# ou6_cs-ctrl_V1_0.net
KiCad netlist of a schematic drawn in EAGLE
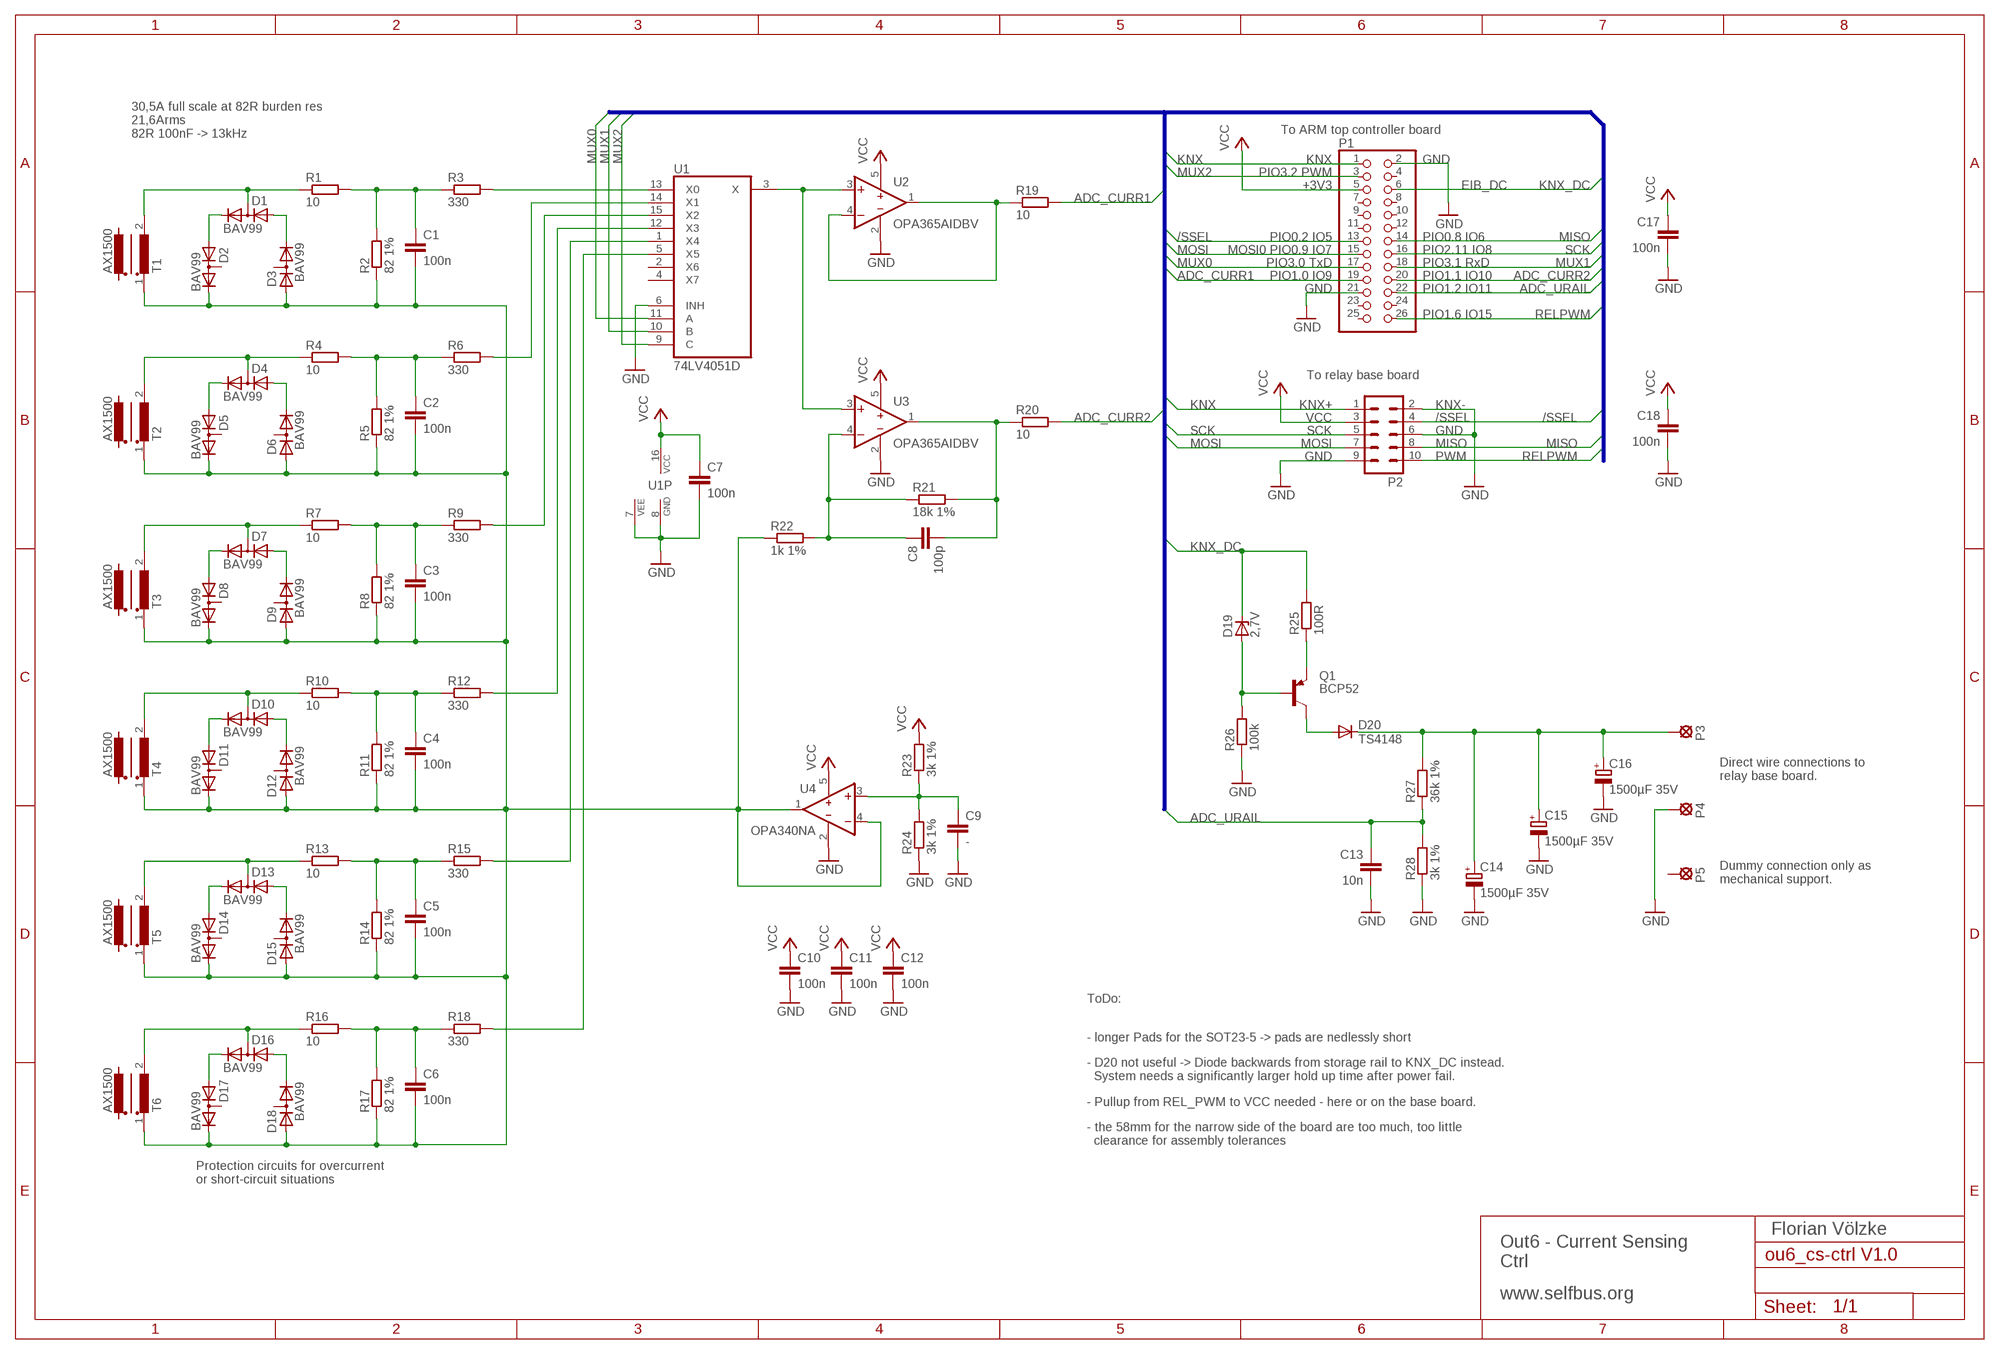
[diagram p0: schematic, sheet 1]

(export (version "E")
  (design (tool "Eeschema 10.0.6"))
  (components
    (comp (ref "C1")
      (value "100n")
      (footprint "eagle-import:R0805M")
      (libsource (lib "eagle-import") (part "C-EUC0805M"))
    )
    (comp (ref "C2")
      (value "100n")
      (footprint "eagle-import:R0805M")
      (libsource (lib "eagle-import") (part "C-EUC0805M"))
    )
    (comp (ref "C3")
      (value "100n")
      (footprint "eagle-import:R0805M")
      (libsource (lib "eagle-import") (part "C-EUC0805M"))
    )
    (comp (ref "C4")
      (value "100n")
      (footprint "eagle-import:R0805M")
      (libsource (lib "eagle-import") (part "C-EUC0805M"))
    )
    (comp (ref "C5")
      (value "100n")
      (footprint "eagle-import:R0805M")
      (libsource (lib "eagle-import") (part "C-EUC0805M"))
    )
    (comp (ref "C6")
      (value "100n")
      (footprint "eagle-import:R0805M")
      (libsource (lib "eagle-import") (part "C-EUC0805M"))
    )
    (comp (ref "C7")
      (value "100n")
      (footprint "eagle-import:R0805M")
      (libsource (lib "eagle-import") (part "C-EUC0805M"))
    )
    (comp (ref "C8")
      (value "100p")
      (footprint "eagle-import:R0805M")
      (libsource (lib "eagle-import") (part "C-EUC0805M"))
    )
    (comp (ref "C9")
      (value "-")
      (footprint "eagle-import:R0805M")
      (libsource (lib "eagle-import") (part "C-EUC0805M"))
    )
    (comp (ref "C10")
      (value "100n")
      (footprint "eagle-import:R0805M")
      (libsource (lib "eagle-import") (part "C-EUC0805M"))
    )
    (comp (ref "C11")
      (value "100n")
      (footprint "eagle-import:R0805M")
      (libsource (lib "eagle-import") (part "C-EUC0805M"))
    )
    (comp (ref "C12")
      (value "100n")
      (footprint "eagle-import:R0805M")
      (libsource (lib "eagle-import") (part "C-EUC0805M"))
    )
    (comp (ref "C13")
      (value "10n")
      (footprint "eagle-import:R0805M")
      (libsource (lib "eagle-import") (part "C-EUC0805M"))
    )
    (comp (ref "C14")
      (value "1500µF 35V")
      (footprint "eagle-import:E5-13-30")
      (libsource (lib "eagle-import") (part "CPOL-EUE5-13-30"))
    )
    (comp (ref "C15")
      (value "1500µF 35V")
      (footprint "eagle-import:E5-13-30")
      (libsource (lib "eagle-import") (part "CPOL-EUE5-13-30"))
    )
    (comp (ref "C16")
      (value "1500µF 35V")
      (footprint "eagle-import:E5-13-30")
      (libsource (lib "eagle-import") (part "CPOL-EUE5-13-30"))
    )
    (comp (ref "C17")
      (value "100n")
      (footprint "eagle-import:R0805M")
      (libsource (lib "eagle-import") (part "C-EUC0805M"))
    )
    (comp (ref "C18")
      (value "100n")
      (footprint "eagle-import:R0805M")
      (libsource (lib "eagle-import") (part "C-EUC0805M"))
    )
    (comp (ref "D1")
      (value "BAV99")
      (footprint "eagle-import:SOT23")
      (libsource (lib "eagle-import") (part "DIODE_2CACA-SOT23"))
    )
    (comp (ref "D2")
      (value "BAV99")
      (footprint "eagle-import:SOT23")
      (libsource (lib "eagle-import") (part "DIODE_2CACA-SOT23"))
    )
    (comp (ref "D3")
      (value "BAV99")
      (footprint "eagle-import:SOT23")
      (libsource (lib "eagle-import") (part "DIODE_2CACA-SOT23"))
    )
    (comp (ref "D4")
      (value "BAV99")
      (footprint "eagle-import:SOT23")
      (libsource (lib "eagle-import") (part "DIODE_2CACA-SOT23"))
    )
    (comp (ref "D5")
      (value "BAV99")
      (footprint "eagle-import:SOT23")
      (libsource (lib "eagle-import") (part "DIODE_2CACA-SOT23"))
    )
    (comp (ref "D6")
      (value "BAV99")
      (footprint "eagle-import:SOT23")
      (libsource (lib "eagle-import") (part "DIODE_2CACA-SOT23"))
    )
    (comp (ref "D7")
      (value "BAV99")
      (footprint "eagle-import:SOT23")
      (libsource (lib "eagle-import") (part "DIODE_2CACA-SOT23"))
    )
    (comp (ref "D8")
      (value "BAV99")
      (footprint "eagle-import:SOT23")
      (libsource (lib "eagle-import") (part "DIODE_2CACA-SOT23"))
    )
    (comp (ref "D9")
      (value "BAV99")
      (footprint "eagle-import:SOT23")
      (libsource (lib "eagle-import") (part "DIODE_2CACA-SOT23"))
    )
    (comp (ref "D10")
      (value "BAV99")
      (footprint "eagle-import:SOT23")
      (libsource (lib "eagle-import") (part "DIODE_2CACA-SOT23"))
    )
    (comp (ref "D11")
      (value "BAV99")
      (footprint "eagle-import:SOT23")
      (libsource (lib "eagle-import") (part "DIODE_2CACA-SOT23"))
    )
    (comp (ref "D12")
      (value "BAV99")
      (footprint "eagle-import:SOT23")
      (libsource (lib "eagle-import") (part "DIODE_2CACA-SOT23"))
    )
    (comp (ref "D13")
      (value "BAV99")
      (footprint "eagle-import:SOT23")
      (libsource (lib "eagle-import") (part "DIODE_2CACA-SOT23"))
    )
    (comp (ref "D14")
      (value "BAV99")
      (footprint "eagle-import:SOT23")
      (libsource (lib "eagle-import") (part "DIODE_2CACA-SOT23"))
    )
    (comp (ref "D15")
      (value "BAV99")
      (footprint "eagle-import:SOT23")
      (libsource (lib "eagle-import") (part "DIODE_2CACA-SOT23"))
    )
    (comp (ref "D16")
      (value "BAV99")
      (footprint "eagle-import:SOT23")
      (libsource (lib "eagle-import") (part "DIODE_2CACA-SOT23"))
    )
    (comp (ref "D17")
      (value "BAV99")
      (footprint "eagle-import:SOT23")
      (libsource (lib "eagle-import") (part "DIODE_2CACA-SOT23"))
    )
    (comp (ref "D18")
      (value "BAV99")
      (footprint "eagle-import:SOT23")
      (libsource (lib "eagle-import") (part "DIODE_2CACA-SOT23"))
    )
    (comp (ref "D19")
      (value "2,7V")
      (footprint "eagle-import:SOT23")
      (libsource (lib "eagle-import") (part "ZENER-DIODESOT23"))
    )
    (comp (ref "D20")
      (value "TS4148")
      (footprint "eagle-import:MINIMELF")
      (libsource (lib "eagle-import") (part "DIODE-MINIMELF"))
    )
    (comp (ref "P1")
      (value "PINHD-2X13SMD")
      (footprint "eagle-import:2X13SMD")
      (libsource (lib "eagle-import") (part "PINHD-2X13SMD"))
    )
    (comp (ref "P2")
      (value "ML10")
      (footprint "eagle-import:ML10")
      (libsource (lib "eagle-import") (part "ML10"))
    )
    (comp (ref "P3")
      (value "SE1.5")
      (footprint "eagle-import:SE15")
      (libsource (lib "eagle-import") (part "SE1.5"))
    )
    (comp (ref "P4")
      (value "SE1.5")
      (footprint "eagle-import:SE15")
      (libsource (lib "eagle-import") (part "SE1.5"))
    )
    (comp (ref "P5")
      (value "SE1.5")
      (footprint "eagle-import:SE15")
      (libsource (lib "eagle-import") (part "SE1.5"))
    )
    (comp (ref "Q1")
      (value "BCP52")
      (footprint "eagle-import:SOT223")
      (libsource (lib "eagle-import") (part "FZT753SMD"))
    )
    (comp (ref "R1")
      (value "10")
      (footprint "eagle-import:R0805M")
      (libsource (lib "eagle-import") (part "R-EU_R0805M"))
    )
    (comp (ref "R2")
      (value "82 1%")
      (footprint "eagle-import:R0805M")
      (libsource (lib "eagle-import") (part "R-EU_R0805M"))
    )
    (comp (ref "R3")
      (value "330")
      (footprint "eagle-import:R0805M")
      (libsource (lib "eagle-import") (part "R-EU_R0805M"))
    )
    (comp (ref "R4")
      (value "10")
      (footprint "eagle-import:R0805M")
      (libsource (lib "eagle-import") (part "R-EU_R0805M"))
    )
    (comp (ref "R5")
      (value "82 1%")
      (footprint "eagle-import:R0805M")
      (libsource (lib "eagle-import") (part "R-EU_R0805M"))
    )
    (comp (ref "R6")
      (value "330")
      (footprint "eagle-import:R0805M")
      (libsource (lib "eagle-import") (part "R-EU_R0805M"))
    )
    (comp (ref "R7")
      (value "10")
      (footprint "eagle-import:R0805M")
      (libsource (lib "eagle-import") (part "R-EU_R0805M"))
    )
    (comp (ref "R8")
      (value "82 1%")
      (footprint "eagle-import:R0805M")
      (libsource (lib "eagle-import") (part "R-EU_R0805M"))
    )
    (comp (ref "R9")
      (value "330")
      (footprint "eagle-import:R0805M")
      (libsource (lib "eagle-import") (part "R-EU_R0805M"))
    )
    (comp (ref "R10")
      (value "10")
      (footprint "eagle-import:R0805M")
      (libsource (lib "eagle-import") (part "R-EU_R0805M"))
    )
    (comp (ref "R11")
      (value "82 1%")
      (footprint "eagle-import:R0805M")
      (libsource (lib "eagle-import") (part "R-EU_R0805M"))
    )
    (comp (ref "R12")
      (value "330")
      (footprint "eagle-import:R0805M")
      (libsource (lib "eagle-import") (part "R-EU_R0805M"))
    )
    (comp (ref "R13")
      (value "10")
      (footprint "eagle-import:R0805M")
      (libsource (lib "eagle-import") (part "R-EU_R0805M"))
    )
    (comp (ref "R14")
      (value "82 1%")
      (footprint "eagle-import:R0805M")
      (libsource (lib "eagle-import") (part "R-EU_R0805M"))
    )
    (comp (ref "R15")
      (value "330")
      (footprint "eagle-import:R0805M")
      (libsource (lib "eagle-import") (part "R-EU_R0805M"))
    )
    (comp (ref "R16")
      (value "10")
      (footprint "eagle-import:R0805M")
      (libsource (lib "eagle-import") (part "R-EU_R0805M"))
    )
    (comp (ref "R17")
      (value "82 1%")
      (footprint "eagle-import:R0805M")
      (libsource (lib "eagle-import") (part "R-EU_R0805M"))
    )
    (comp (ref "R18")
      (value "330")
      (footprint "eagle-import:R0805M")
      (libsource (lib "eagle-import") (part "R-EU_R0805M"))
    )
    (comp (ref "R19")
      (value "10")
      (footprint "eagle-import:R0805M")
      (libsource (lib "eagle-import") (part "R-EU_R0805M"))
    )
    (comp (ref "R20")
      (value "10")
      (footprint "eagle-import:R0805M")
      (libsource (lib "eagle-import") (part "R-EU_R0805M"))
    )
    (comp (ref "R21")
      (value "18k 1%")
      (footprint "eagle-import:R0805M")
      (libsource (lib "eagle-import") (part "R-EU_R0805M"))
    )
    (comp (ref "R22")
      (value "1k 1%")
      (footprint "eagle-import:R0805M")
      (libsource (lib "eagle-import") (part "R-EU_R0805M"))
    )
    (comp (ref "R23")
      (value "3k 1%")
      (footprint "eagle-import:R0805M")
      (libsource (lib "eagle-import") (part "R-EU_R0805M"))
    )
    (comp (ref "R24")
      (value "3k 1%")
      (footprint "eagle-import:R0805M")
      (libsource (lib "eagle-import") (part "R-EU_R0805M"))
    )
    (comp (ref "R25")
      (value "100R")
      (footprint "eagle-import:R0805M")
      (libsource (lib "eagle-import") (part "R-EU_R0805M"))
    )
    (comp (ref "R26")
      (value "100k")
      (footprint "eagle-import:R0805M")
      (libsource (lib "eagle-import") (part "R-EU_R0805M"))
    )
    (comp (ref "R27")
      (value "36k 1%")
      (footprint "eagle-import:R0805M")
      (libsource (lib "eagle-import") (part "R-EU_R0805M"))
    )
    (comp (ref "R28")
      (value "3k 1%")
      (footprint "eagle-import:R0805M")
      (libsource (lib "eagle-import") (part "R-EU_R0805M"))
    )
    (comp (ref "T1")
      (value "AX1500")
      (footprint "eagle-import:SMALLXFORMER")
      (libsource (lib "eagle-import") (part "STROMWANDLERTALEMA_AX1500"))
    )
    (comp (ref "T2")
      (value "AX1500")
      (footprint "eagle-import:SMALLXFORMER")
      (libsource (lib "eagle-import") (part "STROMWANDLERTALEMA_AX1500"))
    )
    (comp (ref "T3")
      (value "AX1500")
      (footprint "eagle-import:SMALLXFORMER")
      (libsource (lib "eagle-import") (part "STROMWANDLERTALEMA_AX1500"))
    )
    (comp (ref "T4")
      (value "AX1500")
      (footprint "eagle-import:SMALLXFORMER")
      (libsource (lib "eagle-import") (part "STROMWANDLERTALEMA_AX1500"))
    )
    (comp (ref "T5")
      (value "AX1500")
      (footprint "eagle-import:SMALLXFORMER")
      (libsource (lib "eagle-import") (part "STROMWANDLERTALEMA_AX1500"))
    )
    (comp (ref "T6")
      (value "AX1500")
      (footprint "eagle-import:SMALLXFORMER")
      (libsource (lib "eagle-import") (part "STROMWANDLERTALEMA_AX1500"))
    )
    (comp (ref "U1")
      (value "74LV4051D")
      (footprint "eagle-import:SO16")
      (libsource (lib "eagle-import") (part "4051D"))
    )
    (comp (ref "U2")
      (value "OPA365AIDBV")
      (footprint "eagle-import:SOT23-5")
      (libsource (lib "eagle-import") (part "LTC2050CS5"))
    )
    (comp (ref "U3")
      (value "OPA365AIDBV")
      (footprint "eagle-import:SOT23-5")
      (libsource (lib "eagle-import") (part "LTC2050CS5"))
    )
    (comp (ref "U4")
      (value "OPA340NA")
      (footprint "eagle-import:SOT23-5")
      (libsource (lib "eagle-import") (part "LTC2050CS5"))
    )
  )
  (nets
    (net (code "1") (name "/ADC_CURR1") (class "Default")
      (node (ref "P1") (pin "19") (pinfunction "19_19") (pintype "passive"))
      (node (ref "R19") (pin "2") (pinfunction "2_2") (pintype "passive"))
    )
    (net (code "2") (name "/ADC_CURR2") (class "Default")
      (node (ref "P1") (pin "20") (pinfunction "20_20") (pintype "passive"))
      (node (ref "R20") (pin "2") (pinfunction "2_2") (pintype "passive"))
    )
    (net (code "3") (name "/ADC_URAIL") (class "Default")
      (node (ref "C13") (pin "1") (pinfunction "1_1") (pintype "passive"))
      (node (ref "P1") (pin "22") (pinfunction "22_22") (pintype "passive"))
      (node (ref "R27") (pin "1") (pinfunction "1_1") (pintype "passive"))
      (node (ref "R28") (pin "2") (pinfunction "2_2") (pintype "passive"))
    )
    (net (code "4") (name "/KNX") (class "Default")
      (node (ref "P1") (pin "1") (pinfunction "1_1") (pintype "passive"))
      (node (ref "P2") (pin "1") (pinfunction "1_1") (pintype "passive"))
    )
    (net (code "5") (name "/KNX_DC") (class "Default")
      (node (ref "D19") (pin "3") (pinfunction "C_3") (pintype "passive"))
      (node (ref "P1") (pin "6") (pinfunction "6_6") (pintype "passive"))
      (node (ref "R25") (pin "2") (pinfunction "2_2") (pintype "passive"))
    )
    (net (code "6") (name "/MISO") (class "Default")
      (node (ref "P1") (pin "14") (pinfunction "14_14") (pintype "passive"))
      (node (ref "P2") (pin "8") (pinfunction "8_8") (pintype "passive"))
    )
    (net (code "7") (name "/MOSI") (class "Default")
      (node (ref "P1") (pin "15") (pinfunction "15_15") (pintype "passive"))
      (node (ref "P2") (pin "7") (pinfunction "7_7") (pintype "passive"))
    )
    (net (code "8") (name "/MUX0") (class "Default")
      (node (ref "P1") (pin "17") (pinfunction "17_17") (pintype "passive"))
      (node (ref "U1") (pin "11") (pinfunction "A_11") (pintype "input"))
    )
    (net (code "9") (name "/MUX1") (class "Default")
      (node (ref "P1") (pin "18") (pinfunction "18_18") (pintype "passive"))
      (node (ref "U1") (pin "10") (pinfunction "B_10") (pintype "input"))
    )
    (net (code "10") (name "/MUX2") (class "Default")
      (node (ref "P1") (pin "3") (pinfunction "3_3") (pintype "passive"))
      (node (ref "U1") (pin "9") (pinfunction "C_9") (pintype "input"))
    )
    (net (code "11") (name "/RELPWM") (class "Default")
      (node (ref "P1") (pin "26") (pinfunction "26_26") (pintype "passive"))
      (node (ref "P2") (pin "10") (pinfunction "10_10") (pintype "passive"))
    )
    (net (code "12") (name "/SCK") (class "Default")
      (node (ref "P1") (pin "16") (pinfunction "16_16") (pintype "passive"))
      (node (ref "P2") (pin "5") (pinfunction "5_5") (pintype "passive"))
    )
    (net (code "13") (name "/{slash}SSEL") (class "Default")
      (node (ref "P1") (pin "13") (pinfunction "13_13") (pintype "passive"))
      (node (ref "P2") (pin "4") (pinfunction "4_4") (pintype "passive"))
    )
    (net (code "14") (name "GND") (class "Default")
      (node (ref "C10") (pin "2") (pinfunction "2_2") (pintype "passive"))
      (node (ref "C11") (pin "2") (pinfunction "2_2") (pintype "passive"))
      (node (ref "C12") (pin "2") (pinfunction "2_2") (pintype "passive"))
      (node (ref "C13") (pin "2") (pinfunction "2_2") (pintype "passive"))
      (node (ref "C14") (pin "-") (pinfunction "-_-") (pintype "passive"))
      (node (ref "C15") (pin "-") (pinfunction "-_-") (pintype "passive"))
      (node (ref "C16") (pin "-") (pinfunction "-_-") (pintype "passive"))
      (node (ref "C17") (pin "2") (pinfunction "2_2") (pintype "passive"))
      (node (ref "C18") (pin "2") (pinfunction "2_2") (pintype "passive"))
      (node (ref "C7") (pin "2") (pinfunction "2_2") (pintype "passive"))
      (node (ref "C9") (pin "2") (pinfunction "2_2") (pintype "passive"))
      (node (ref "P1") (pin "2") (pinfunction "2_2") (pintype "passive"))
      (node (ref "P1") (pin "21") (pinfunction "21_21") (pintype "passive"))
      (node (ref "P2") (pin "2") (pinfunction "2_2") (pintype "passive"))
      (node (ref "P2") (pin "6") (pinfunction "6_6") (pintype "passive"))
      (node (ref "P2") (pin "9") (pinfunction "9_9") (pintype "passive"))
      (node (ref "P4") (pin "MP") (pinfunction "MP_MP") (pintype "passive"))
      (node (ref "R24") (pin "1") (pinfunction "1_1") (pintype "passive"))
      (node (ref "R26") (pin "1") (pinfunction "1_1") (pintype "passive"))
      (node (ref "R28") (pin "1") (pinfunction "1_1") (pintype "passive"))
      (node (ref "U1") (pin "6") (pinfunction "INH_6") (pintype "input"))
      (node (ref "U1") (pin "7") (pinfunction "VEE_7") (pintype "power_in"))
      (node (ref "U1") (pin "8") (pinfunction "GND_8") (pintype "power_in"))
      (node (ref "U2") (pin "2") (pinfunction "V-_2") (pintype "power_in"))
      (node (ref "U3") (pin "2") (pinfunction "V-_2") (pintype "power_in"))
      (node (ref "U4") (pin "2") (pinfunction "V-_2") (pintype "power_in"))
    )
    (net (code "15") (name "Net-(C1-Pad1)") (class "Default")
      (node (ref "C1") (pin "1") (pinfunction "1_1") (pintype "passive"))
      (node (ref "R1") (pin "2") (pinfunction "2_2") (pintype "passive"))
      (node (ref "R2") (pin "2") (pinfunction "2_2") (pintype "passive"))
      (node (ref "R3") (pin "1") (pinfunction "1_1") (pintype "passive"))
    )
    (net (code "16") (name "Net-(C2-Pad1)") (class "Default")
      (node (ref "C2") (pin "1") (pinfunction "1_1") (pintype "passive"))
      (node (ref "R4") (pin "2") (pinfunction "2_2") (pintype "passive"))
      (node (ref "R5") (pin "2") (pinfunction "2_2") (pintype "passive"))
      (node (ref "R6") (pin "1") (pinfunction "1_1") (pintype "passive"))
    )
    (net (code "17") (name "Net-(C3-Pad1)") (class "Default")
      (node (ref "C3") (pin "1") (pinfunction "1_1") (pintype "passive"))
      (node (ref "R7") (pin "2") (pinfunction "2_2") (pintype "passive"))
      (node (ref "R8") (pin "2") (pinfunction "2_2") (pintype "passive"))
      (node (ref "R9") (pin "1") (pinfunction "1_1") (pintype "passive"))
    )
    (net (code "18") (name "Net-(C4-Pad1)") (class "Default")
      (node (ref "C4") (pin "1") (pinfunction "1_1") (pintype "passive"))
      (node (ref "R10") (pin "2") (pinfunction "2_2") (pintype "passive"))
      (node (ref "R11") (pin "2") (pinfunction "2_2") (pintype "passive"))
      (node (ref "R12") (pin "1") (pinfunction "1_1") (pintype "passive"))
    )
    (net (code "19") (name "Net-(C5-Pad1)") (class "Default")
      (node (ref "C5") (pin "1") (pinfunction "1_1") (pintype "passive"))
      (node (ref "R13") (pin "2") (pinfunction "2_2") (pintype "passive"))
      (node (ref "R14") (pin "2") (pinfunction "2_2") (pintype "passive"))
      (node (ref "R15") (pin "1") (pinfunction "1_1") (pintype "passive"))
    )
    (net (code "20") (name "Net-(C6-Pad1)") (class "Default")
      (node (ref "C6") (pin "1") (pinfunction "1_1") (pintype "passive"))
      (node (ref "R16") (pin "2") (pinfunction "2_2") (pintype "passive"))
      (node (ref "R17") (pin "2") (pinfunction "2_2") (pintype "passive"))
      (node (ref "R18") (pin "1") (pinfunction "1_1") (pintype "passive"))
    )
    (net (code "21") (name "Net-(C14-Pad+)") (class "Default")
      (node (ref "C14") (pin "+") (pinfunction "+_+") (pintype "passive"))
      (node (ref "C15") (pin "+") (pinfunction "+_+") (pintype "passive"))
      (node (ref "C16") (pin "+") (pinfunction "+_+") (pintype "passive"))
      (node (ref "D20") (pin "C") (pinfunction "C_C") (pintype "passive"))
      (node (ref "P3") (pin "MP") (pinfunction "MP_MP") (pintype "passive"))
      (node (ref "R27") (pin "2") (pinfunction "2_2") (pintype "passive"))
    )
    (net (code "22") (name "Net-(D1-A)") (class "Default")
      (node (ref "D1") (pin "1") (pinfunction "A_1") (pintype "passive"))
      (node (ref "D3") (pin "2") (pinfunction "C_2") (pintype "passive"))
    )
    (net (code "23") (name "Net-(D1-AC)") (class "Default")
      (node (ref "D1") (pin "3") (pinfunction "AC_3") (pintype "passive"))
      (node (ref "R1") (pin "1") (pinfunction "1_1") (pintype "passive"))
      (node (ref "T1") (pin "2") (pinfunction "W1E_2") (pintype "passive"))
    )
    (net (code "24") (name "Net-(D1-C)") (class "Default")
      (node (ref "D1") (pin "2") (pinfunction "C_2") (pintype "passive"))
      (node (ref "D2") (pin "1") (pinfunction "A_1") (pintype "passive"))
    )
    (net (code "25") (name "Net-(D4-A)") (class "Default")
      (node (ref "D4") (pin "1") (pinfunction "A_1") (pintype "passive"))
      (node (ref "D6") (pin "2") (pinfunction "C_2") (pintype "passive"))
    )
    (net (code "26") (name "Net-(D4-AC)") (class "Default")
      (node (ref "D4") (pin "3") (pinfunction "AC_3") (pintype "passive"))
      (node (ref "R4") (pin "1") (pinfunction "1_1") (pintype "passive"))
      (node (ref "T2") (pin "2") (pinfunction "W1E_2") (pintype "passive"))
    )
    (net (code "27") (name "Net-(D4-C)") (class "Default")
      (node (ref "D4") (pin "2") (pinfunction "C_2") (pintype "passive"))
      (node (ref "D5") (pin "1") (pinfunction "A_1") (pintype "passive"))
    )
    (net (code "28") (name "Net-(D7-A)") (class "Default")
      (node (ref "D7") (pin "1") (pinfunction "A_1") (pintype "passive"))
      (node (ref "D9") (pin "2") (pinfunction "C_2") (pintype "passive"))
    )
    (net (code "29") (name "Net-(D7-AC)") (class "Default")
      (node (ref "D7") (pin "3") (pinfunction "AC_3") (pintype "passive"))
      (node (ref "R7") (pin "1") (pinfunction "1_1") (pintype "passive"))
      (node (ref "T3") (pin "2") (pinfunction "W1E_2") (pintype "passive"))
    )
    (net (code "30") (name "Net-(D7-C)") (class "Default")
      (node (ref "D7") (pin "2") (pinfunction "C_2") (pintype "passive"))
      (node (ref "D8") (pin "1") (pinfunction "A_1") (pintype "passive"))
    )
    (net (code "31") (name "Net-(D10-A)") (class "Default")
      (node (ref "D10") (pin "1") (pinfunction "A_1") (pintype "passive"))
      (node (ref "D12") (pin "2") (pinfunction "C_2") (pintype "passive"))
    )
    (net (code "32") (name "Net-(D10-AC)") (class "Default")
      (node (ref "D10") (pin "3") (pinfunction "AC_3") (pintype "passive"))
      (node (ref "R10") (pin "1") (pinfunction "1_1") (pintype "passive"))
      (node (ref "T4") (pin "2") (pinfunction "W1E_2") (pintype "passive"))
    )
    (net (code "33") (name "Net-(D10-C)") (class "Default")
      (node (ref "D10") (pin "2") (pinfunction "C_2") (pintype "passive"))
      (node (ref "D11") (pin "1") (pinfunction "A_1") (pintype "passive"))
    )
    (net (code "34") (name "Net-(D11-C)") (class "Default")
      (node (ref "C1") (pin "2") (pinfunction "2_2") (pintype "passive"))
      (node (ref "C2") (pin "2") (pinfunction "2_2") (pintype "passive"))
      (node (ref "C3") (pin "2") (pinfunction "2_2") (pintype "passive"))
      (node (ref "C4") (pin "2") (pinfunction "2_2") (pintype "passive"))
      (node (ref "C5") (pin "2") (pinfunction "2_2") (pintype "passive"))
      (node (ref "C6") (pin "2") (pinfunction "2_2") (pintype "passive"))
      (node (ref "D11") (pin "2") (pinfunction "C_2") (pintype "passive"))
      (node (ref "D12") (pin "1") (pinfunction "A_1") (pintype "passive"))
      (node (ref "D14") (pin "2") (pinfunction "C_2") (pintype "passive"))
      (node (ref "D15") (pin "1") (pinfunction "A_1") (pintype "passive"))
      (node (ref "D17") (pin "2") (pinfunction "C_2") (pintype "passive"))
      (node (ref "D18") (pin "1") (pinfunction "A_1") (pintype "passive"))
      (node (ref "D2") (pin "2") (pinfunction "C_2") (pintype "passive"))
      (node (ref "D3") (pin "1") (pinfunction "A_1") (pintype "passive"))
      (node (ref "D5") (pin "2") (pinfunction "C_2") (pintype "passive"))
      (node (ref "D6") (pin "1") (pinfunction "A_1") (pintype "passive"))
      (node (ref "D8") (pin "2") (pinfunction "C_2") (pintype "passive"))
      (node (ref "D9") (pin "1") (pinfunction "A_1") (pintype "passive"))
      (node (ref "R11") (pin "1") (pinfunction "1_1") (pintype "passive"))
      (node (ref "R14") (pin "1") (pinfunction "1_1") (pintype "passive"))
      (node (ref "R17") (pin "1") (pinfunction "1_1") (pintype "passive"))
      (node (ref "R2") (pin "1") (pinfunction "1_1") (pintype "passive"))
      (node (ref "R22") (pin "1") (pinfunction "1_1") (pintype "passive"))
      (node (ref "R5") (pin "1") (pinfunction "1_1") (pintype "passive"))
      (node (ref "R8") (pin "1") (pinfunction "1_1") (pintype "passive"))
      (node (ref "T1") (pin "1") (pinfunction "W1A_1") (pintype "passive"))
      (node (ref "T2") (pin "1") (pinfunction "W1A_1") (pintype "passive"))
      (node (ref "T3") (pin "1") (pinfunction "W1A_1") (pintype "passive"))
      (node (ref "T4") (pin "1") (pinfunction "W1A_1") (pintype "passive"))
      (node (ref "T5") (pin "1") (pinfunction "W1A_1") (pintype "passive"))
      (node (ref "T6") (pin "1") (pinfunction "W1A_1") (pintype "passive"))
      (node (ref "U4") (pin "1") (pinfunction "OUT_1") (pintype "output"))
      (node (ref "U4") (pin "4") (pinfunction "-IN_4") (pintype "input"))
    )
    (net (code "35") (name "Net-(D13-A)") (class "Default")
      (node (ref "D13") (pin "1") (pinfunction "A_1") (pintype "passive"))
      (node (ref "D15") (pin "2") (pinfunction "C_2") (pintype "passive"))
    )
    (net (code "36") (name "Net-(D13-AC)") (class "Default")
      (node (ref "D13") (pin "3") (pinfunction "AC_3") (pintype "passive"))
      (node (ref "R13") (pin "1") (pinfunction "1_1") (pintype "passive"))
      (node (ref "T5") (pin "2") (pinfunction "W1E_2") (pintype "passive"))
    )
    (net (code "37") (name "Net-(D13-C)") (class "Default")
      (node (ref "D13") (pin "2") (pinfunction "C_2") (pintype "passive"))
      (node (ref "D14") (pin "1") (pinfunction "A_1") (pintype "passive"))
    )
    (net (code "38") (name "Net-(D16-A)") (class "Default")
      (node (ref "D16") (pin "1") (pinfunction "A_1") (pintype "passive"))
      (node (ref "D18") (pin "2") (pinfunction "C_2") (pintype "passive"))
    )
    (net (code "39") (name "Net-(D16-AC)") (class "Default")
      (node (ref "D16") (pin "3") (pinfunction "AC_3") (pintype "passive"))
      (node (ref "R16") (pin "1") (pinfunction "1_1") (pintype "passive"))
      (node (ref "T6") (pin "2") (pinfunction "W1E_2") (pintype "passive"))
    )
    (net (code "40") (name "Net-(D16-C)") (class "Default")
      (node (ref "D16") (pin "2") (pinfunction "C_2") (pintype "passive"))
      (node (ref "D17") (pin "1") (pinfunction "A_1") (pintype "passive"))
    )
    (net (code "41") (name "Net-(D19-A)") (class "Default")
      (node (ref "D19") (pin "1") (pinfunction "A_1") (pintype "passive"))
      (node (ref "Q1") (pin "1") (pinfunction "B_1") (pintype "passive"))
      (node (ref "R26") (pin "2") (pinfunction "2_2") (pintype "passive"))
    )
    (net (code "42") (name "Net-(D20-PadA)") (class "Default")
      (node (ref "D20") (pin "A") (pinfunction "A_A") (pintype "passive"))
      (node (ref "Q1") (pin "2") (pinfunction "C_2") (pintype "passive"))
      (node (ref "Q1") (pin "4") (pinfunction "C_4") (pintype "passive"))
    )
    (net (code "43") (name "Net-(Q1-E)") (class "Default")
      (node (ref "Q1") (pin "3") (pinfunction "E_3") (pintype "passive"))
      (node (ref "R25") (pin "1") (pinfunction "1_1") (pintype "passive"))
    )
    (net (code "44") (name "Net-(U1A-X)") (class "Default")
      (node (ref "U1") (pin "3") (pinfunction "X_3") (pintype "bidirectional"))
      (node (ref "U2") (pin "3") (pinfunction "+IN_3") (pintype "input"))
      (node (ref "U3") (pin "3") (pinfunction "+IN_3") (pintype "input"))
    )
    (net (code "45") (name "Net-(U1A-X0)") (class "Default")
      (node (ref "R3") (pin "2") (pinfunction "2_2") (pintype "passive"))
      (node (ref "U1") (pin "13") (pinfunction "X0_13") (pintype "bidirectional"))
    )
    (net (code "46") (name "Net-(U1A-X1)") (class "Default")
      (node (ref "R6") (pin "2") (pinfunction "2_2") (pintype "passive"))
      (node (ref "U1") (pin "14") (pinfunction "X1_14") (pintype "bidirectional"))
    )
    (net (code "47") (name "Net-(U1A-X2)") (class "Default")
      (node (ref "R9") (pin "2") (pinfunction "2_2") (pintype "passive"))
      (node (ref "U1") (pin "15") (pinfunction "X2_15") (pintype "bidirectional"))
    )
    (net (code "48") (name "Net-(U1A-X3)") (class "Default")
      (node (ref "R12") (pin "2") (pinfunction "2_2") (pintype "passive"))
      (node (ref "U1") (pin "12") (pinfunction "X3_12") (pintype "bidirectional"))
    )
    (net (code "49") (name "Net-(U1A-X4)") (class "Default")
      (node (ref "R15") (pin "2") (pinfunction "2_2") (pintype "passive"))
      (node (ref "U1") (pin "1") (pinfunction "X4_1") (pintype "bidirectional"))
    )
    (net (code "50") (name "Net-(U1A-X5)") (class "Default")
      (node (ref "R18") (pin "2") (pinfunction "2_2") (pintype "passive"))
      (node (ref "U1") (pin "5") (pinfunction "X5_5") (pintype "bidirectional"))
    )
    (net (code "51") (name "Net-(U2--IN)") (class "Default")
      (node (ref "R19") (pin "1") (pinfunction "1_1") (pintype "passive"))
      (node (ref "U2") (pin "1") (pinfunction "OUT_1") (pintype "output"))
      (node (ref "U2") (pin "4") (pinfunction "-IN_4") (pintype "input"))
    )
    (net (code "52") (name "Net-(U3--IN)") (class "Default")
      (node (ref "C8") (pin "1") (pinfunction "1_1") (pintype "passive"))
      (node (ref "R21") (pin "1") (pinfunction "1_1") (pintype "passive"))
      (node (ref "R22") (pin "2") (pinfunction "2_2") (pintype "passive"))
      (node (ref "U3") (pin "4") (pinfunction "-IN_4") (pintype "input"))
    )
    (net (code "53") (name "Net-(U3-OUT)") (class "Default")
      (node (ref "C8") (pin "2") (pinfunction "2_2") (pintype "passive"))
      (node (ref "R20") (pin "1") (pinfunction "1_1") (pintype "passive"))
      (node (ref "R21") (pin "2") (pinfunction "2_2") (pintype "passive"))
      (node (ref "U3") (pin "1") (pinfunction "OUT_1") (pintype "output"))
    )
    (net (code "54") (name "Net-(U4-+IN)") (class "Default")
      (node (ref "C9") (pin "1") (pinfunction "1_1") (pintype "passive"))
      (node (ref "R23") (pin "1") (pinfunction "1_1") (pintype "passive"))
      (node (ref "R24") (pin "2") (pinfunction "2_2") (pintype "passive"))
      (node (ref "U4") (pin "3") (pinfunction "+IN_3") (pintype "input"))
    )
    (net (code "55") (name "VCC") (class "Default")
      (node (ref "C10") (pin "1") (pinfunction "1_1") (pintype "passive"))
      (node (ref "C11") (pin "1") (pinfunction "1_1") (pintype "passive"))
      (node (ref "C12") (pin "1") (pinfunction "1_1") (pintype "passive"))
      (node (ref "C17") (pin "1") (pinfunction "1_1") (pintype "passive"))
      (node (ref "C18") (pin "1") (pinfunction "1_1") (pintype "passive"))
      (node (ref "C7") (pin "1") (pinfunction "1_1") (pintype "passive"))
      (node (ref "P1") (pin "5") (pinfunction "5_5") (pintype "passive"))
      (node (ref "P2") (pin "3") (pinfunction "3_3") (pintype "passive"))
      (node (ref "R23") (pin "2") (pinfunction "2_2") (pintype "passive"))
      (node (ref "U1") (pin "16") (pinfunction "VCC_16") (pintype "power_in"))
      (node (ref "U2") (pin "5") (pinfunction "V+_5") (pintype "power_in"))
      (node (ref "U3") (pin "5") (pinfunction "V+_5") (pintype "power_in"))
      (node (ref "U4") (pin "5") (pinfunction "V+_5") (pintype "power_in"))
    )
    (net (code "56") (name "unconnected-(D2-AC-Pad3)") (class "Default")
      (node (ref "D2") (pin "3") (pinfunction "AC_3") (pintype "passive"))
    )
    (net (code "57") (name "unconnected-(D3-AC-Pad3)") (class "Default")
      (node (ref "D3") (pin "3") (pinfunction "AC_3") (pintype "passive"))
    )
    (net (code "58") (name "unconnected-(D5-AC-Pad3)") (class "Default")
      (node (ref "D5") (pin "3") (pinfunction "AC_3") (pintype "passive"))
    )
    (net (code "59") (name "unconnected-(D6-AC-Pad3)") (class "Default")
      (node (ref "D6") (pin "3") (pinfunction "AC_3") (pintype "passive"))
    )
    (net (code "60") (name "unconnected-(D8-AC-Pad3)") (class "Default")
      (node (ref "D8") (pin "3") (pinfunction "AC_3") (pintype "passive"))
    )
    (net (code "61") (name "unconnected-(D9-AC-Pad3)") (class "Default")
      (node (ref "D9") (pin "3") (pinfunction "AC_3") (pintype "passive"))
    )
    (net (code "62") (name "unconnected-(D11-AC-Pad3)") (class "Default")
      (node (ref "D11") (pin "3") (pinfunction "AC_3") (pintype "passive"))
    )
    (net (code "63") (name "unconnected-(D12-AC-Pad3)") (class "Default")
      (node (ref "D12") (pin "3") (pinfunction "AC_3") (pintype "passive"))
    )
    (net (code "64") (name "unconnected-(D14-AC-Pad3)") (class "Default")
      (node (ref "D14") (pin "3") (pinfunction "AC_3") (pintype "passive"))
    )
    (net (code "65") (name "unconnected-(D15-AC-Pad3)") (class "Default")
      (node (ref "D15") (pin "3") (pinfunction "AC_3") (pintype "passive"))
    )
    (net (code "66") (name "unconnected-(D17-AC-Pad3)") (class "Default")
      (node (ref "D17") (pin "3") (pinfunction "AC_3") (pintype "passive"))
    )
    (net (code "67") (name "unconnected-(D18-AC-Pad3)") (class "Default")
      (node (ref "D18") (pin "3") (pinfunction "AC_3") (pintype "passive"))
    )
    (net (code "68") (name "unconnected-(P1-Pad4)") (class "Default")
      (node (ref "P1") (pin "4") (pinfunction "4_4") (pintype "passive"))
    )
    (net (code "69") (name "unconnected-(P1-Pad7)") (class "Default")
      (node (ref "P1") (pin "7") (pinfunction "7_7") (pintype "passive"))
    )
    (net (code "70") (name "unconnected-(P1-Pad8)") (class "Default")
      (node (ref "P1") (pin "8") (pinfunction "8_8") (pintype "passive"))
    )
    (net (code "71") (name "unconnected-(P1-Pad9)") (class "Default")
      (node (ref "P1") (pin "9") (pinfunction "9_9") (pintype "passive"))
    )
    (net (code "72") (name "unconnected-(P1-Pad10)") (class "Default")
      (node (ref "P1") (pin "10") (pinfunction "10_10") (pintype "passive"))
    )
    (net (code "73") (name "unconnected-(P1-Pad11)") (class "Default")
      (node (ref "P1") (pin "11") (pinfunction "11_11") (pintype "passive"))
    )
    (net (code "74") (name "unconnected-(P1-Pad12)") (class "Default")
      (node (ref "P1") (pin "12") (pinfunction "12_12") (pintype "passive"))
    )
    (net (code "75") (name "unconnected-(P1-Pad23)") (class "Default")
      (node (ref "P1") (pin "23") (pinfunction "23_23") (pintype "passive"))
    )
    (net (code "76") (name "unconnected-(P1-Pad24)") (class "Default")
      (node (ref "P1") (pin "24") (pinfunction "24_24") (pintype "passive"))
    )
    (net (code "77") (name "unconnected-(P1-Pad25)") (class "Default")
      (node (ref "P1") (pin "25") (pinfunction "25_25") (pintype "passive"))
    )
    (net (code "78") (name "unconnected-(P5-PadMP)") (class "Default")
      (node (ref "P5") (pin "MP") (pinfunction "MP_MP") (pintype "passive"))
    )
    (net (code "79") (name "unconnected-(U1A-X6-Pad2)") (class "Default")
      (node (ref "U1") (pin "2") (pinfunction "X6_2") (pintype "bidirectional"))
    )
    (net (code "80") (name "unconnected-(U1A-X7-Pad4)") (class "Default")
      (node (ref "U1") (pin "4") (pinfunction "X7_4") (pintype "bidirectional"))
    )
  )
)
